# autres_ressouces_sch_ma.net
KiCad netlist of a schematic drawn in Altium Designer
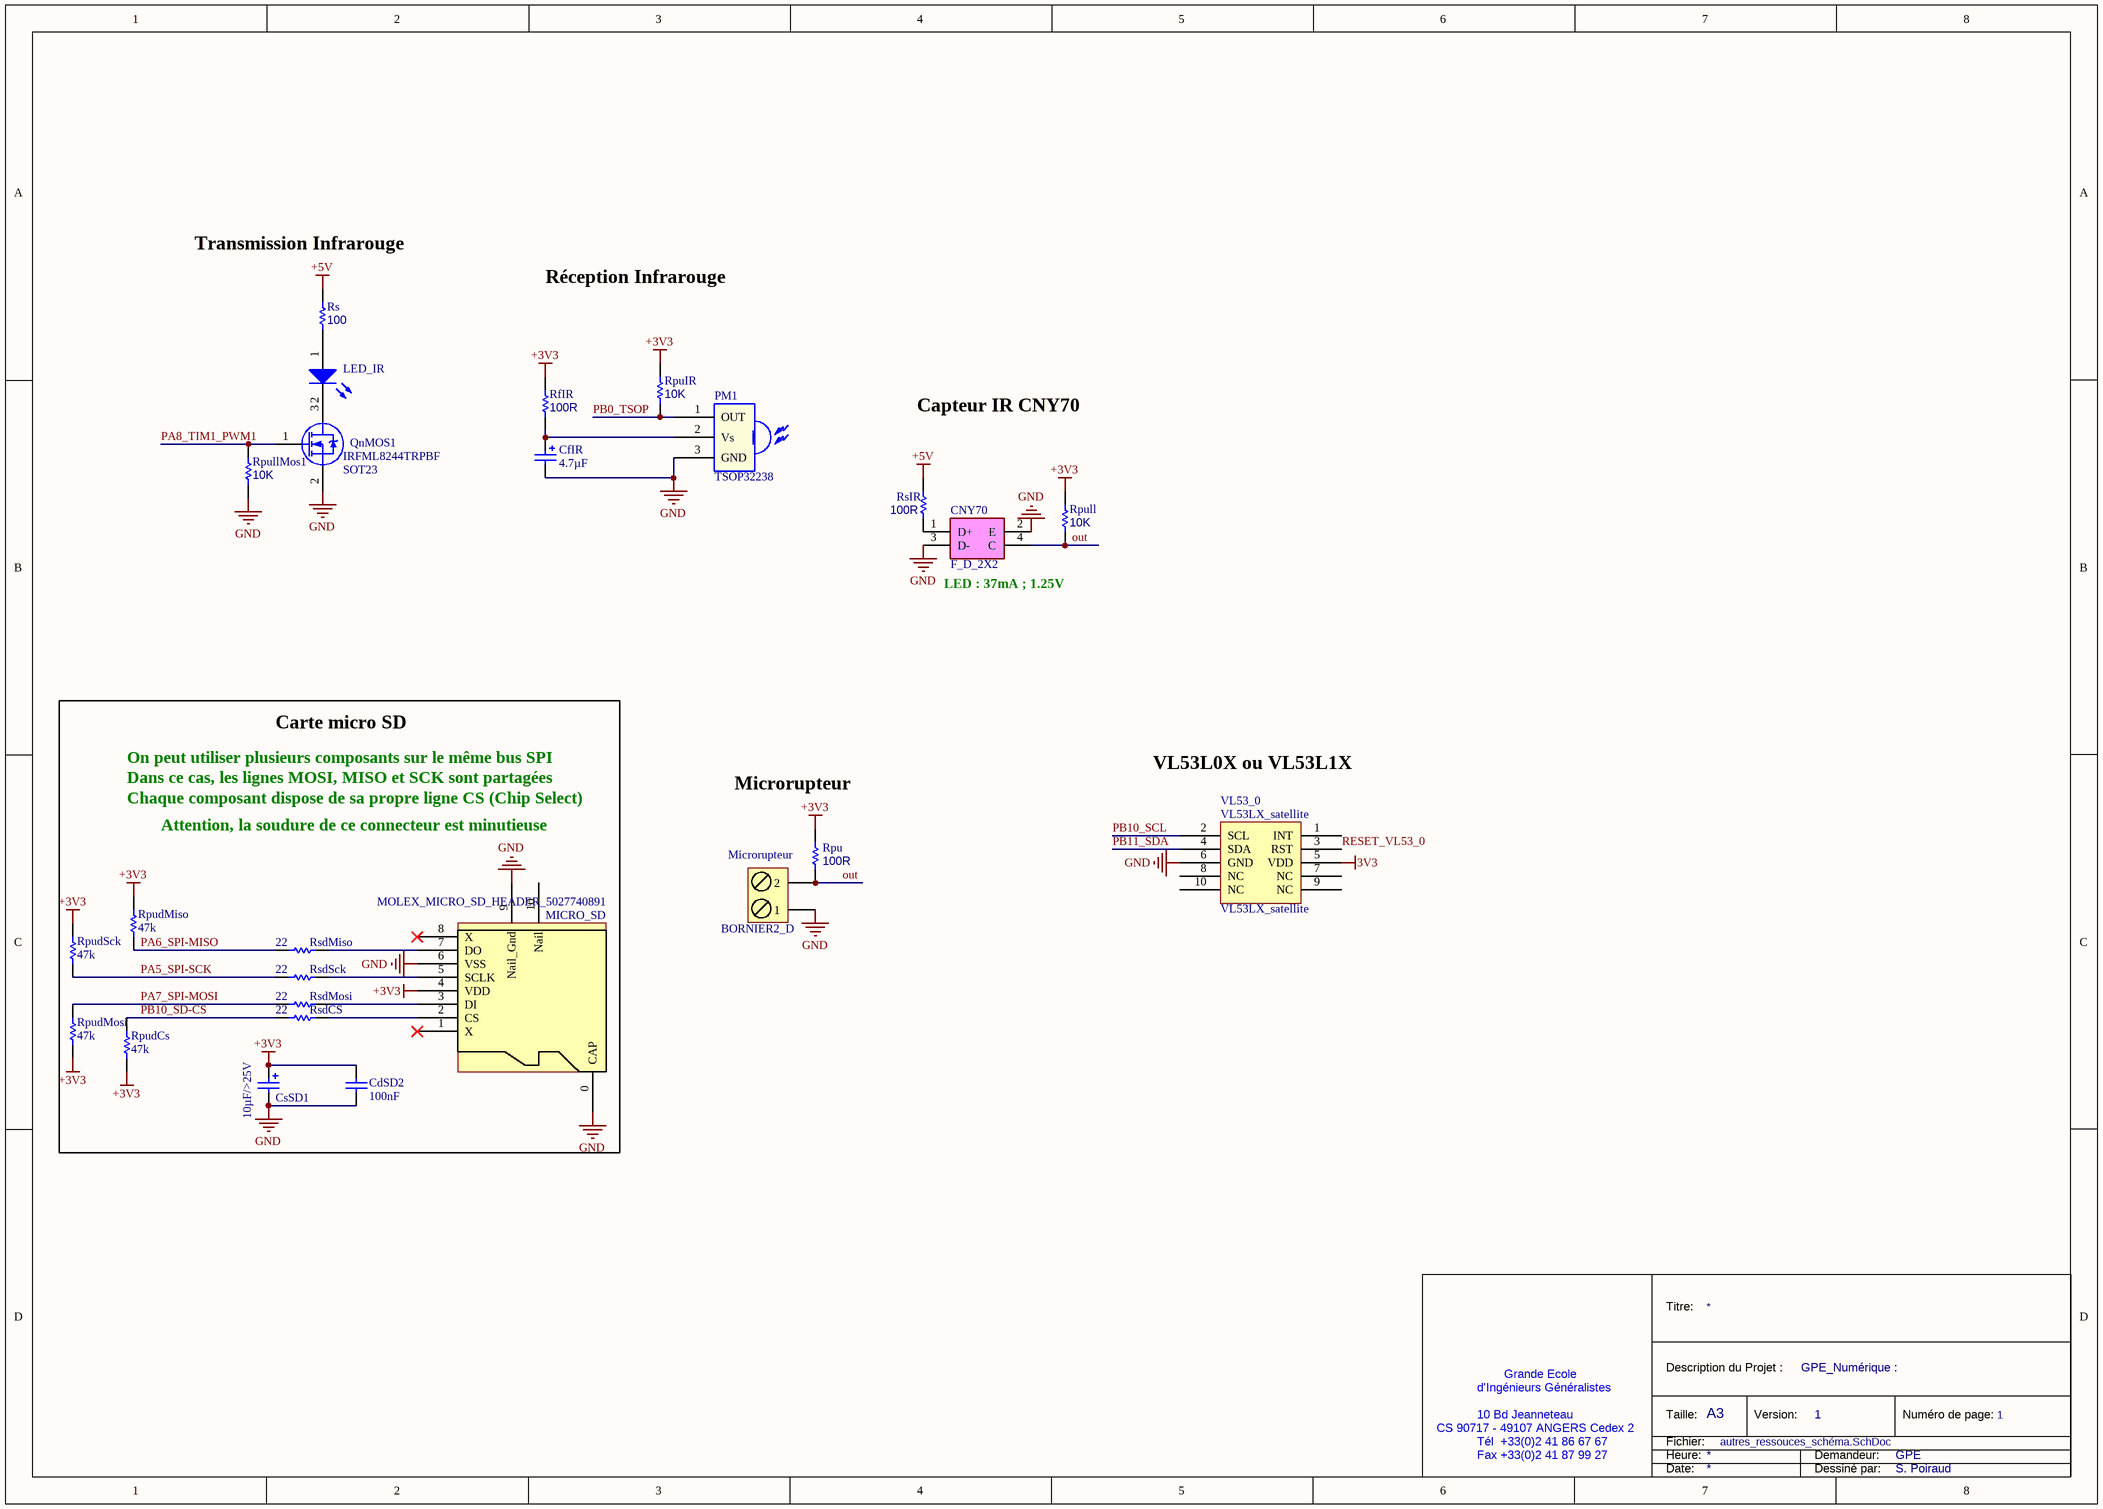
[diagram p0: autres_ressouces_schéma.SchDoc]

(export (version "E")
  (design (tool "Eeschema 10.0.6"))
  (components
    (comp (ref "CdSD2")
      (value "100nF")
      (footprint "CONDENSATEUR_CERAMIQUE_RADIAL_5.08")
      (description "Capacitor")
      (fields (field (name "PUBLISHER") "Altium Limited"))
      (libsource (lib "_ROBOT") (part "Condensateur"))
    )
    (comp (ref "CfIR")
      (value "4.7µF")
      (footprint "CONDENSATEUR_POLARISE_ELECTROLYTIQUE_RADIAL_2.0/5.08")
      (description "CONDENSATEUR POLARISE ELECTROLYTIQUE RADIAL 2.0/5.08")
      (fields (field (name "Comment") "CONDENSATEUR_POL_ELECTROLY_RAD_2.0/5.08"))
      (libsource (lib "composants passifs") (part "CONDENSATEUR_POL_ELECTROLY_RAD_2.0/5.08"))
    )
    (comp (ref "CNY70")
      (value "BARRETTE 2 CONTACTS 2 RANGEES FEMELLE DROITE")
      (footprint "BARRETTE_2X2_F_D")
      (fields (field (name "TYPE") "F_D_2X2"))
      (libsource (lib "connecteurs") (part "BARRETTE_2 CONTACTS_2 RANGEES_FEMELLE_DROITE"))
    )
    (comp (ref "CsSD1")
      (value "10µF/>25V")
      (footprint "CONDENSATEUR_POLARISE_ELECTROLYTIQUE_RADIAL_2.0/5.08")
      (description "CONDENSATEUR POLARISE ELECTROLYTIQUE RADIAL 2.0/5.08")
      (fields (field (name "Comment") "CONDENSATEUR_POL_ELECTROLY_RAD_2.0/5.08"))
      (libsource (lib "composants passifs") (part "CONDENSATEUR_POL_ELECTROLY_RAD_2.0/5.08"))
    )
    (comp (ref "D2")
      (value "LED_3MM")
      (footprint "LED_3MM")
      (description "LED 3MM - ROUGE/VERTE/JAUNE")
      (fields (field (name "TYPE") "LED_IR"))
      (libsource (lib "affichage") (part "LED_3MM"))
    )
    (comp (ref "Microrupteur")
      (value "BORNIER2 DROIT A VIS")
      (footprint "BORNIER2_A_VIS")
      (description "BORNIER 2 PLOTS DROIT A VIS 5.08mm")
      (fields (field (name "TYPE") "BORNIER2_D"))
      (libsource (lib "connecteurs") (part "BORNIER2_DROIT_A VIS"))
    )
    (comp (ref "MICRO_SD")
      (value "MOLEX_MICRO_SD_HEADER_5027740891")
      (footprint "MOLEX_MICRO_SD_HEADER_5027740891")
      (libsource (lib "Connecteur") (part "MOLEX_MICRO_SD_HEADER_5027740891"))
    )
    (comp (ref "PM1")
      (value "RECEPTEUR_INFRAROUGE_TSOP32238")
      (footprint "RECEPTEUR_INFRAROUGE_TSOP32238")
      (description "RECEPTEUR_INFRAROUGE_TSOP32238_38kHz")
      (fields (field (name "TYPE") "TSOP32238"))
      (libsource (lib "affichage") (part "RECEPTEUR_INFRAROUGE_TSOP32238_38kHz"))
    )
    (comp (ref "QnMOS1")
      (value "TRANSISTOR_MOSFET-N_SOT23_GSD")
      (footprint "TRANSISTOR_MOSFET-N_SOT23_GSD")
      (description "TRANSISTOR MOSFET CANAL N BOITIER SOT23_GSD")
      (fields (field (name "TYPE") "IRFML8244TRPBF") (field (name "PACKAGE") "SOT23"))
      (libsource (lib "composants actifs") (part "TRANSISTOR_MOSFET-N_SOT23_GSD"))
    )
    (comp (ref "RfIR")
      (value "100R")
      (footprint "RESISTANCE_1/4W")
      (description "RESISTANCE TRAVERSANTE AXIALE 1/4W")
      (fields (field (name "Comment") "RESISTANCE_AXIALE_1/4W"))
      (libsource (lib "composants passifs") (part "RESISTANCE_AXIALE_1/4W"))
    )
    (comp (ref "Rpu")
      (value "100R")
      (footprint "RESISTANCE_1/4W")
      (description "RESISTANCE TRAVERSANTE AXIALE 1/4W")
      (fields (field (name "Comment") "RESISTANCE_AXIALE_1/4W"))
      (libsource (lib "composants passifs") (part "RESISTANCE_AXIALE_1/4W"))
    )
    (comp (ref "RpudCs")
      (value "47k")
      (footprint "RESISTANCE_1/4W")
      (description "Resistor")
      (fields (field (name "PUBLISHER") "Altium Limited"))
      (libsource (lib "_ROBOT") (part "Resistor"))
    )
    (comp (ref "RpudMiso")
      (value "47k")
      (footprint "RESISTANCE_1/4W")
      (description "Resistor")
      (fields (field (name "PUBLISHER") "Altium Limited"))
      (libsource (lib "_ROBOT") (part "Resistor"))
    )
    (comp (ref "RpudMosi")
      (value "47k")
      (footprint "RESISTANCE_1/4W")
      (description "Resistor")
      (fields (field (name "PUBLISHER") "Altium Limited"))
      (libsource (lib "_ROBOT") (part "Resistor"))
    )
    (comp (ref "RpudSck")
      (value "47k")
      (footprint "RESISTANCE_1/4W")
      (description "Resistor")
      (fields (field (name "PUBLISHER") "Altium Limited"))
      (libsource (lib "_ROBOT") (part "Resistor"))
    )
    (comp (ref "RpuIR")
      (value "10K")
      (footprint "RESISTANCE_1/4W")
      (description "RESISTANCE TRAVERSANTE AXIALE 1/4W")
      (fields (field (name "Comment") "RESISTANCE_AXIALE_1/4W"))
      (libsource (lib "composants passifs") (part "RESISTANCE_AXIALE_1/4W"))
    )
    (comp (ref "Rpull")
      (value "10K")
      (footprint "RESISTANCE_1/4W")
      (description "RESISTANCE TRAVERSANTE AXIALE 1/4W")
      (fields (field (name "Comment") "RESISTANCE_AXIALE_1/4W"))
      (libsource (lib "composants passifs") (part "RESISTANCE_AXIALE_1/4W"))
    )
    (comp (ref "RpullMos1")
      (value "10K")
      (footprint "RESISTANCE_1/4W")
      (description "RESISTANCE TRAVERSANTE AXIALE 1/4W")
      (fields (field (name "Comment") "RESISTANCE_AXIALE_1/4W"))
      (libsource (lib "composants passifs") (part "RESISTANCE_AXIALE_1/4W"))
    )
    (comp (ref "Rs")
      (value "100")
      (footprint "RESISTANCE_1/4W")
      (description "RESISTANCE TRAVERSANTE AXIALE 1/4W")
      (fields (field (name "Comment") "RESISTANCE_AXIALE_1/4W"))
      (libsource (lib "composants passifs") (part "RESISTANCE_AXIALE_1/4W"))
    )
    (comp (ref "RsdCS")
      (value "22")
      (footprint "RESISTANCE_1/4W")
      (description "Resistor")
      (fields (field (name "PUBLISHER") "Altium Limited"))
      (libsource (lib "_ROBOT") (part "Resistor"))
    )
    (comp (ref "RsdMiso")
      (value "22")
      (footprint "RESISTANCE_1/4W")
      (description "Resistor")
      (fields (field (name "PUBLISHER") "Altium Limited"))
      (libsource (lib "_ROBOT") (part "Resistor"))
    )
    (comp (ref "RsdMosi")
      (value "22")
      (footprint "RESISTANCE_1/4W")
      (description "Resistor")
      (fields (field (name "PUBLISHER") "Altium Limited"))
      (libsource (lib "_ROBOT") (part "Resistor"))
    )
    (comp (ref "RsdSck")
      (value "22")
      (footprint "RESISTANCE_1/4W")
      (description "Resistor")
      (fields (field (name "PUBLISHER") "Altium Limited"))
      (libsource (lib "_ROBOT") (part "Resistor"))
    )
    (comp (ref "RsIR")
      (value "100R")
      (footprint "RESISTANCE_1/4W")
      (description "RESISTANCE TRAVERSANTE AXIALE 1/4W")
      (fields (field (name "Comment") "RESISTANCE_AXIALE_1/4W"))
      (libsource (lib "composants passifs") (part "RESISTANCE_AXIALE_1/4W"))
    )
    (comp (ref "VL53_0")
      (value "VL53LX_satellite")
      (footprint "VL53LX - Satellite - HDR2x3")
      (libsource (lib "_ROBOT") (part "VL53LX_satellite"))
    )
  )
  (nets
    (net (code "1") (name "+3V3") (class "Default")
      (node (ref "CdSD2") (pin "2") (pinfunction "2_2") (pintype "passive"))
      (node (ref "CsSD1") (pin "1") (pinfunction "1_1") (pintype "passive"))
      (node (ref "MICRO_SD") (pin "4") (pinfunction "VDD_4") (pintype "passive"))
      (node (ref "RfIR") (pin "1") (pinfunction "1_1") (pintype "passive"))
      (node (ref "Rpu") (pin "1") (pinfunction "1_1") (pintype "passive"))
      (node (ref "RpuIR") (pin "1") (pinfunction "1_1") (pintype "passive"))
      (node (ref "RpudCs") (pin "1") (pinfunction "1_1") (pintype "passive"))
      (node (ref "RpudMiso") (pin "2") (pinfunction "2_2") (pintype "passive"))
      (node (ref "RpudMosi") (pin "1") (pinfunction "1_1") (pintype "passive"))
      (node (ref "RpudSck") (pin "2") (pinfunction "2_2") (pintype "passive"))
      (node (ref "Rpull") (pin "1") (pinfunction "1_1") (pintype "passive"))
    )
    (net (code "2") (name "+5V") (class "Default")
      (node (ref "Rs") (pin "2") (pinfunction "2_2") (pintype "passive"))
      (node (ref "RsIR") (pin "1") (pinfunction "1_1") (pintype "passive"))
    )
    (net (code "3") (name "/PA5_SPI-SCK") (class "Default")
      (node (ref "RpudSck") (pin "1") (pinfunction "1_1") (pintype "passive"))
      (node (ref "RsdSck") (pin "1") (pinfunction "1_1") (pintype "passive"))
    )
    (net (code "4") (name "/PA6_SPI-MISO") (class "Default")
      (node (ref "RpudMiso") (pin "1") (pinfunction "1_1") (pintype "passive"))
      (node (ref "RsdMiso") (pin "1") (pinfunction "1_1") (pintype "passive"))
    )
    (net (code "5") (name "/PA7_SPI-MOSI") (class "Default")
      (node (ref "RpudMosi") (pin "2") (pinfunction "2_2") (pintype "passive"))
      (node (ref "RsdMosi") (pin "1") (pinfunction "1_1") (pintype "passive"))
    )
    (net (code "6") (name "/PA8_TIM1_PWM1") (class "Default")
      (node (ref "QnMOS1") (pin "1") (pinfunction "G_1") (pintype "passive"))
      (node (ref "RpullMos1") (pin "2") (pinfunction "2_2") (pintype "passive"))
    )
    (net (code "7") (name "/PB0_TSOP") (class "Default")
      (node (ref "PM1") (pin "1") (pinfunction "OUT_1") (pintype "passive"))
      (node (ref "RpuIR") (pin "2") (pinfunction "2_2") (pintype "passive"))
    )
    (net (code "8") (name "/PB10_SCL") (class "Default")
      (node (ref "VL53_0") (pin "2") (pinfunction "SCL_2") (pintype "passive"))
    )
    (net (code "9") (name "/PB10_SD-CS") (class "Default")
      (node (ref "RpudCs") (pin "2") (pinfunction "2_2") (pintype "passive"))
      (node (ref "RsdCS") (pin "1") (pinfunction "1_1") (pintype "passive"))
    )
    (net (code "10") (name "/PB11_SDA") (class "Default")
      (node (ref "VL53_0") (pin "4") (pinfunction "SDA_4") (pintype "passive"))
    )
    (net (code "11") (name "/RESET_VL53_0") (class "Default")
      (node (ref "VL53_0") (pin "3") (pinfunction "RST_3") (pintype "passive"))
    )
    (net (code "12") (name "/out") (class "Default")
      (node (ref "CNY70") (pin "4") (pinfunction "C_4") (pintype "passive"))
      (node (ref "Microrupteur") (pin "2") (pinfunction "2_2") (pintype "passive"))
      (node (ref "Rpu") (pin "2") (pinfunction "2_2") (pintype "passive"))
      (node (ref "Rpull") (pin "2") (pinfunction "2_2") (pintype "passive"))
    )
    (net (code "13") (name "3V3") (class "Default")
      (node (ref "VL53_0") (pin "5") (pinfunction "VDD_5") (pintype "passive"))
    )
    (net (code "14") (name "GND") (class "Default")
      (node (ref "CNY70") (pin "2") (pinfunction "E_2") (pintype "passive"))
      (node (ref "CNY70") (pin "3") (pinfunction "D-_3") (pintype "passive"))
      (node (ref "CdSD2") (pin "1") (pinfunction "1_1") (pintype "passive"))
      (node (ref "CfIR") (pin "2") (pinfunction "2_2") (pintype "passive"))
      (node (ref "CsSD1") (pin "2") (pinfunction "2_2") (pintype "passive"))
      (node (ref "MICRO_SD") (pin "0") (pinfunction "CAP_0") (pintype "passive"))
      (node (ref "MICRO_SD") (pin "6") (pinfunction "VSS_6") (pintype "passive"))
      (node (ref "MICRO_SD") (pin "9") (pinfunction "Nail_Gnd_9") (pintype "passive"))
      (node (ref "Microrupteur") (pin "1") (pinfunction "1_1") (pintype "passive"))
      (node (ref "PM1") (pin "3") (pinfunction "GND_3") (pintype "passive"))
      (node (ref "QnMOS1") (pin "2") (pinfunction "S_2") (pintype "passive"))
      (node (ref "RpullMos1") (pin "1") (pinfunction "1_1") (pintype "passive"))
      (node (ref "VL53_0") (pin "6") (pinfunction "GND_6") (pintype "passive"))
    )
    (net (code "15") (name "Net-(CNY70-D+)") (class "Default")
      (node (ref "CNY70") (pin "1") (pinfunction "D+_1") (pintype "passive"))
      (node (ref "RsIR") (pin "2") (pinfunction "2_2") (pintype "passive"))
    )
    (net (code "16") (name "Net-(D2-Pad1)") (class "Default")
      (node (ref "D2") (pin "1") (pinfunction "1_1") (pintype "passive"))
      (node (ref "Rs") (pin "1") (pinfunction "1_1") (pintype "passive"))
    )
    (net (code "17") (name "Net-(MICRO_SD-CS)") (class "Default")
      (node (ref "MICRO_SD") (pin "2") (pinfunction "CS_2") (pintype "passive"))
      (node (ref "RsdCS") (pin "2") (pinfunction "2_2") (pintype "passive"))
    )
    (net (code "18") (name "Net-(MICRO_SD-DI)") (class "Default")
      (node (ref "MICRO_SD") (pin "3") (pinfunction "DI_3") (pintype "passive"))
      (node (ref "RsdMosi") (pin "2") (pinfunction "2_2") (pintype "passive"))
    )
    (net (code "19") (name "Net-(MICRO_SD-DO)") (class "Default")
      (node (ref "MICRO_SD") (pin "7") (pinfunction "DO_7") (pintype "passive"))
      (node (ref "RsdMiso") (pin "2") (pinfunction "2_2") (pintype "passive"))
    )
    (net (code "20") (name "Net-(MICRO_SD-SCLK)") (class "Default")
      (node (ref "MICRO_SD") (pin "5") (pinfunction "SCLK_5") (pintype "passive"))
      (node (ref "RsdSck") (pin "2") (pinfunction "2_2") (pintype "passive"))
    )
    (net (code "21") (name "Net-(PM1-Vs)") (class "Default")
      (node (ref "CfIR") (pin "1") (pinfunction "1_1") (pintype "passive"))
      (node (ref "PM1") (pin "2") (pinfunction "Vs_2") (pintype "passive"))
      (node (ref "RfIR") (pin "2") (pinfunction "2_2") (pintype "passive"))
    )
    (net (code "22") (name "unconnected-(D2-Pad2)") (class "Default")
      (node (ref "D2") (pin "2") (pinfunction "2_2") (pintype "passive"))
    )
    (net (code "23") (name "unconnected-(MICRO_SD-Nail-Pad10)") (class "Default")
      (node (ref "MICRO_SD") (pin "10") (pinfunction "Nail_10") (pintype "passive"))
    )
    (net (code "24") (name "unconnected-(MICRO_SD-X-Pad1)") (class "Default")
      (node (ref "MICRO_SD") (pin "1") (pinfunction "X_1") (pintype "passive+no_connect"))
    )
    (net (code "25") (name "unconnected-(MICRO_SD-X-Pad8)") (class "Default")
      (node (ref "MICRO_SD") (pin "8") (pinfunction "X_8") (pintype "passive+no_connect"))
    )
    (net (code "26") (name "unconnected-(QnMOS1-D-Pad3)") (class "Default")
      (node (ref "QnMOS1") (pin "3") (pinfunction "D_3") (pintype "passive"))
    )
    (net (code "27") (name "unconnected-(VL53_0-INT-Pad1)") (class "Default")
      (node (ref "VL53_0") (pin "1") (pinfunction "INT_1") (pintype "passive"))
    )
    (net (code "28") (name "unconnected-(VL53_0-NC-Pad7)") (class "Default")
      (node (ref "VL53_0") (pin "7") (pinfunction "NC_7") (pintype "passive"))
    )
    (net (code "29") (name "unconnected-(VL53_0-NC-Pad8)") (class "Default")
      (node (ref "VL53_0") (pin "8") (pinfunction "NC_8") (pintype "passive"))
    )
    (net (code "30") (name "unconnected-(VL53_0-NC-Pad9)") (class "Default")
      (node (ref "VL53_0") (pin "9") (pinfunction "NC_9") (pintype "passive"))
    )
    (net (code "31") (name "unconnected-(VL53_0-NC-Pad10)") (class "Default")
      (node (ref "VL53_0") (pin "10") (pinfunction "NC_10") (pintype "passive"))
    )
  )
)
